# Samuel_Quenching.net
KiCad netlist of a schematic drawn in EasyEDA Pro
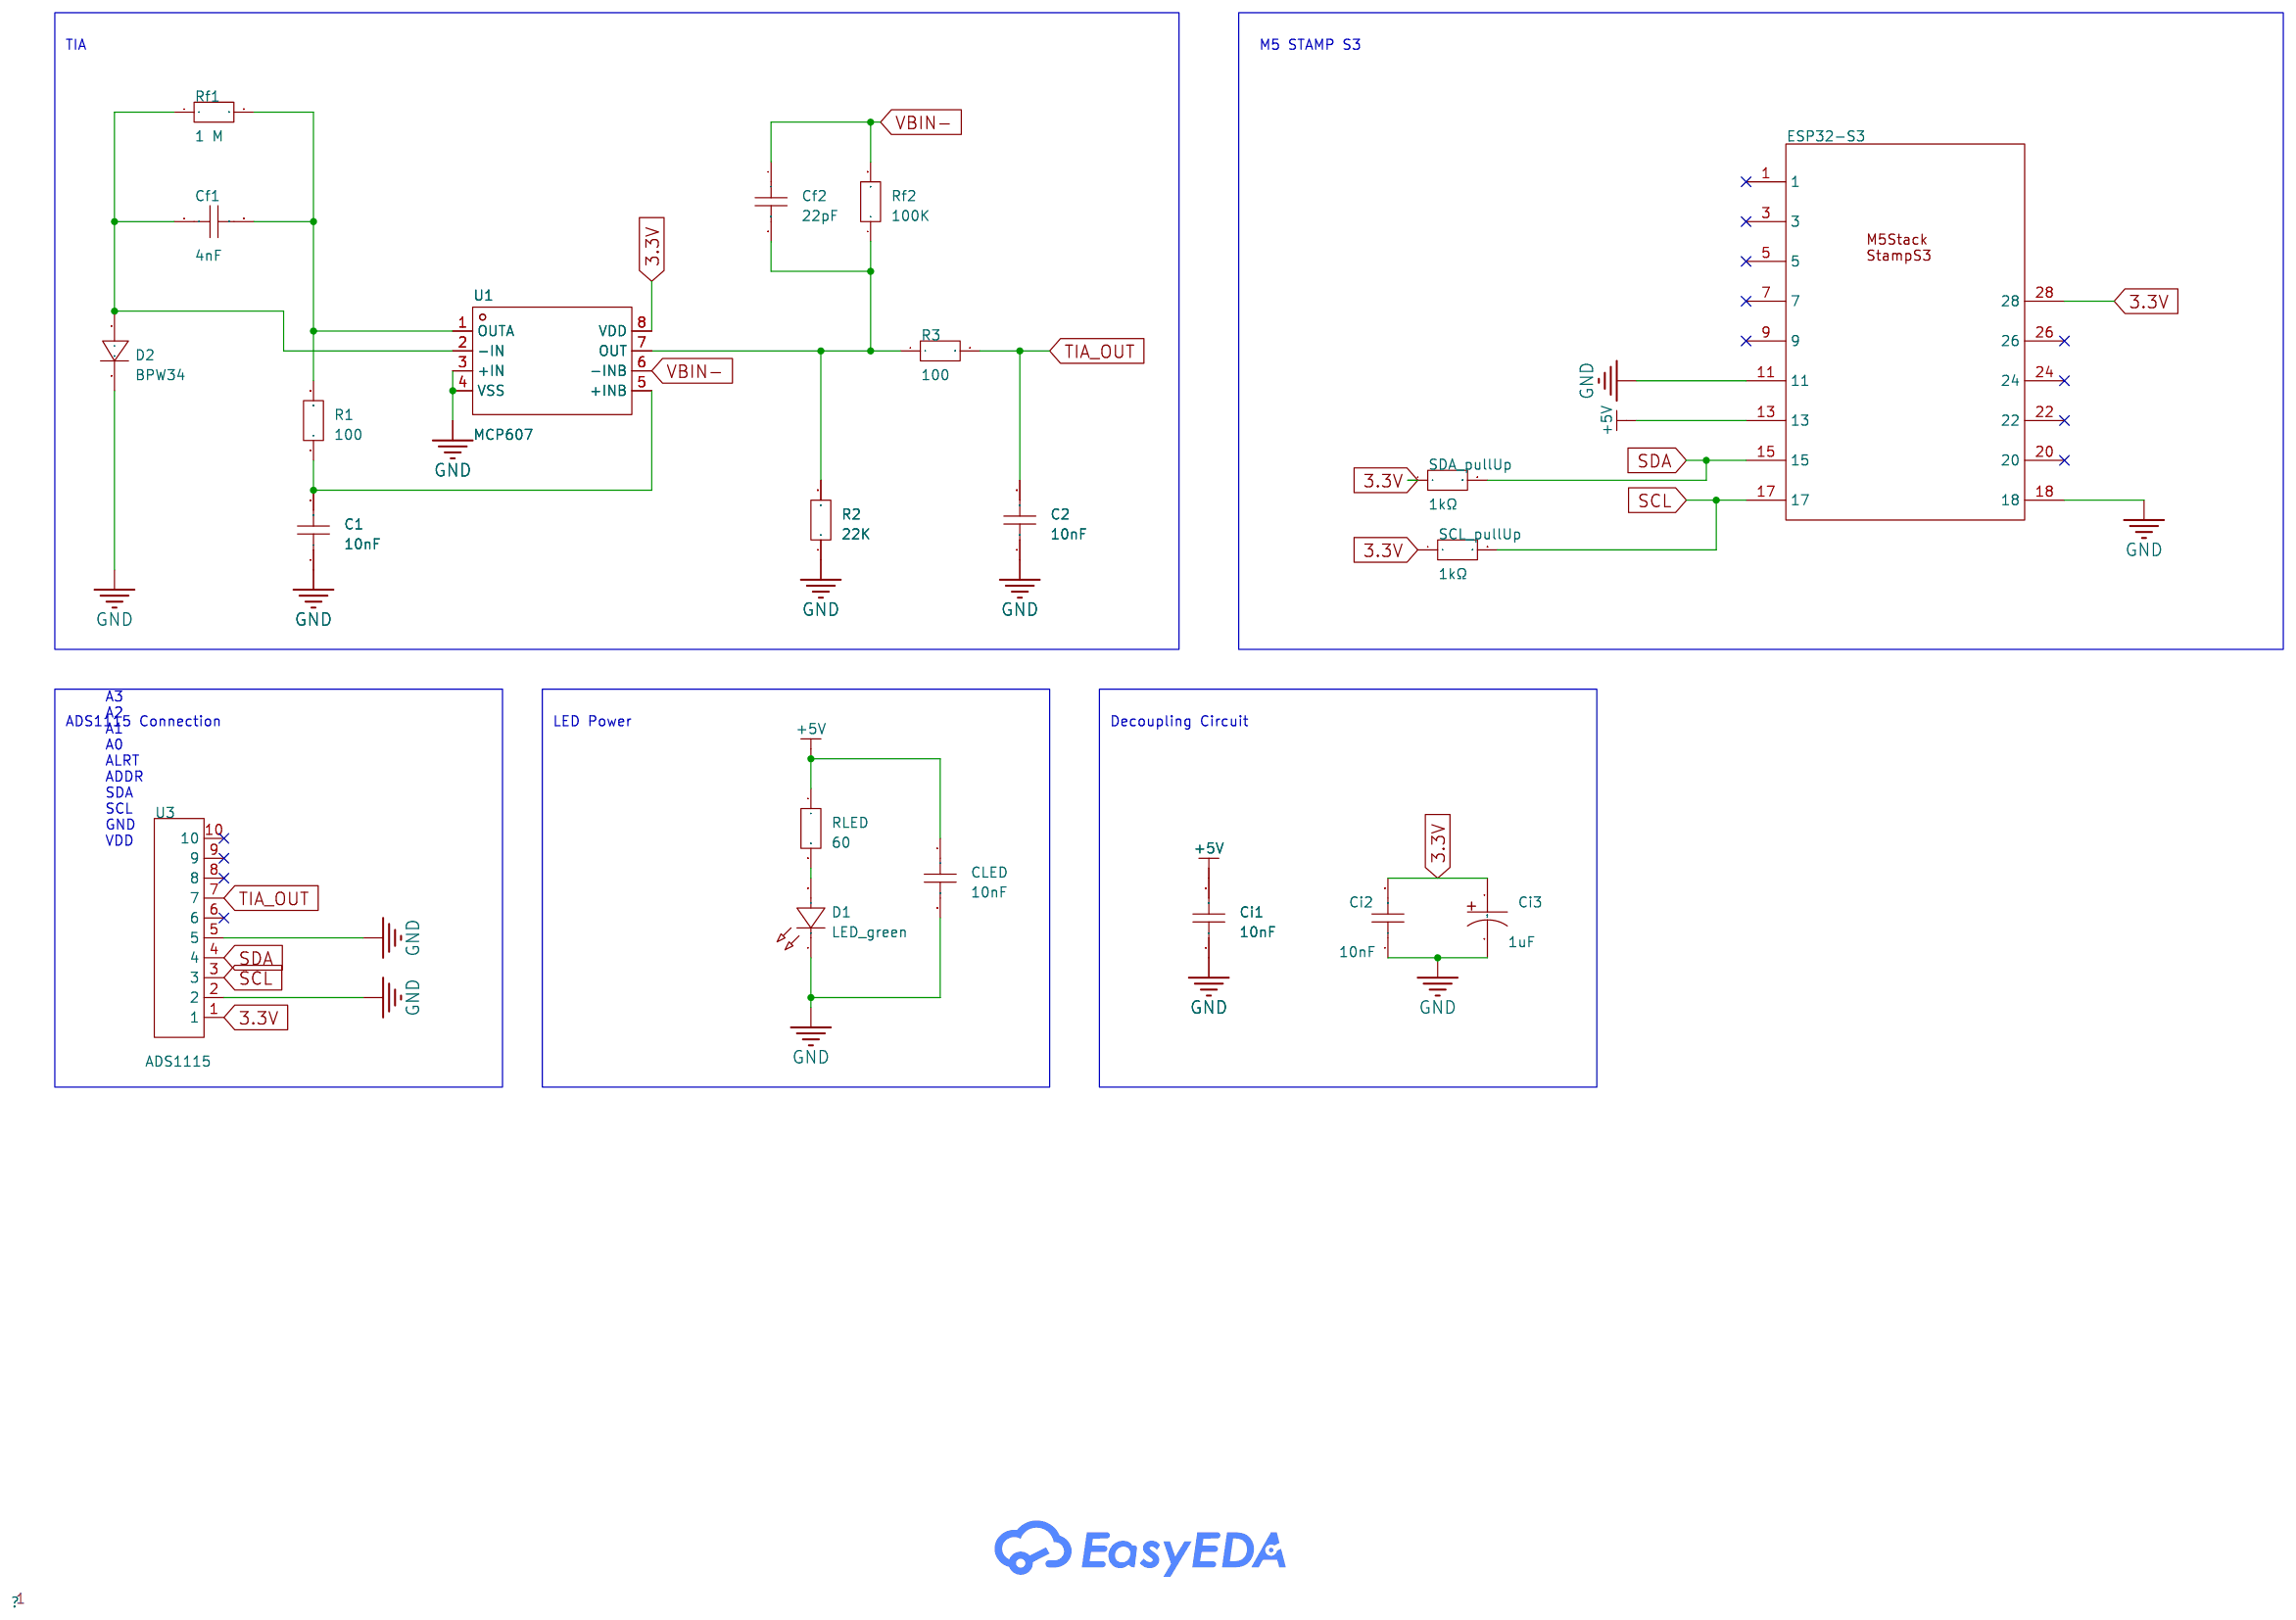
[diagram p0: schematic sheet]

(export (version "E")
  (design (tool "Eeschema 10.0.6"))
  (components
    (comp (ref "C1")
      (value "2.2nF")
      (footprint "easyedapro:CAP-TH_L6.0-W3.0-P5.00-D1.0")
      (fields (field (name "Manufacturer Part") "R06F1B222MN0B0S0N0") (field (name "Manufacturer") "STE(松田)"))
      (libsource (lib "easyedapro") (part "R06F1B222MN0B0S0N0"))
    )
    (comp (ref "C2")
      (value "2.2nF")
      (footprint "easyedapro:CAP-TH_L6.0-W3.0-P5.00-D1.0")
      (fields (field (name "Manufacturer Part") "R06F1B222MN0B0S0N0") (field (name "Manufacturer") "STE(松田)"))
      (libsource (lib "easyedapro") (part "R06F1B222MN0B0S0N0"))
    )
    (comp (ref "Cf1")
      (value "2.2nF")
      (footprint "easyedapro:CAP-TH_L6.0-W3.0-P5.00-D1.0")
      (fields (field (name "Manufacturer Part") "R06F1B222MN0B0S0N0") (field (name "Manufacturer") "STE(松田)"))
      (libsource (lib "easyedapro") (part "R06F1B222MN0B0S0N0"))
    )
    (comp (ref "Cf2")
      (value "2.2nF")
      (footprint "easyedapro:CAP-TH_L6.0-W3.0-P5.00-D1.0")
      (fields (field (name "Manufacturer Part") "R06F1B222MN0B0S0N0") (field (name "Manufacturer") "STE(松田)"))
      (libsource (lib "easyedapro") (part "R06F1B222MN0B0S0N0"))
    )
    (comp (ref "Ci1")
      (value "2.2nF")
      (footprint "easyedapro:CAP-TH_L6.0-W3.0-P5.00-D1.0")
      (fields (field (name "Manufacturer Part") "R06F1B222MN0B0S0N0") (field (name "Manufacturer") "STE(松田)"))
      (libsource (lib "easyedapro") (part "R06F1B222MN0B0S0N0"))
    )
    (comp (ref "Ci2")
      (value "2.2nF")
      (footprint "easyedapro:CAP-TH_L6.0-W3.0-P5.00-D1.0")
      (fields (field (name "Manufacturer Part") "R06F1B222MN0B0S0N0") (field (name "Manufacturer") "STE(松田)"))
      (libsource (lib "easyedapro") (part "R06F1B222MN0B0S0N0"))
    )
    (comp (ref "Ci3")
      (value "20F")
      (footprint "easyedapro:CAP-TH_BD5.0-P2.00-D0.5-FD_CD26G2AM1R0D110T")
      (fields (field (name "Manufacturer Part") "SLA3R8O2060813") (field (name "Manufacturer") "Ymin(永铭)"))
      (libsource (lib "easyedapro") (part "SLA3R8L2060813"))
    )
    (comp (ref "CLED")
      (value "2.2nF")
      (footprint "easyedapro:CAP-TH_L6.0-W3.0-P5.00-D1.0")
      (fields (field (name "Manufacturer Part") "R06F1B222MN0B0S0N0") (field (name "Manufacturer") "STE(松田)"))
      (libsource (lib "easyedapro") (part "R06F1B222MN0B0S0N0"))
    )
    (comp (ref "D1")
      (value "LED_green")
      (footprint "easyedapro:LED-TH_BD3.5-P2.28-3A2K-10")
      (fields
        (field (name "Manufacturer Part") "3A2K-10")
        (field (name "Manufacturer") "Guiguang light(桂光光电)")
      )
      (libsource (lib "easyedapro") (part "3A2K-10"))
    )
    (comp (ref "D2")
      (value "BPW34")
      (footprint "easyedapro:SENSOR-TH_BPW34")
      (fields (field (name "Manufacturer") "VISHAY(威世)"))
      (libsource (lib "easyedapro") (part "BPW34_C85128"))
    )
    (comp (ref "ESP32-S3")
      (value "U2")
      (footprint "easyedapro:M5Stack StampS3")
      (libsource (lib "easyedapro") (part "Esp-S3 M5Stamp"))
    )
    (comp (ref "R1")
      (value "1kΩ")
      (footprint "easyedapro:RES-TH_BD2.3-L6.5-P10.50-D0.5")
      (fields (field (name "Manufacturer Part") "MF1/4W-1KΩ±1%T52") (field (name "Manufacturer") "华星机电"))
      (libsource (lib "easyedapro") (part "MF1/4W-1KΩ±1%T52"))
    )
    (comp (ref "R2")
      (value "1kΩ")
      (footprint "easyedapro:RES-TH_BD2.3-L6.5-P10.50-D0.5")
      (fields (field (name "Manufacturer Part") "MF1/4W-1KΩ±1%T52") (field (name "Manufacturer") "华星机电"))
      (libsource (lib "easyedapro") (part "MF1/4W-1KΩ±1%T52"))
    )
    (comp (ref "R3")
      (value "1kΩ")
      (footprint "easyedapro:RES-TH_BD2.3-L6.5-P10.50-D0.5")
      (fields (field (name "Manufacturer Part") "MF1/4W-1KΩ±1%T52") (field (name "Manufacturer") "华星机电"))
      (libsource (lib "easyedapro") (part "MF1/4W-1KΩ±1%T52"))
    )
    (comp (ref "Rf1")
      (value "1kΩ")
      (footprint "easyedapro:RES-TH_BD2.3-L6.5-P10.50-D0.5")
      (fields (field (name "Manufacturer Part") "MF1/4W-1KΩ±1%T52") (field (name "Manufacturer") "华星机电"))
      (libsource (lib "easyedapro") (part "MF1/4W-1KΩ±1%T52"))
    )
    (comp (ref "Rf2")
      (value "1kΩ")
      (footprint "easyedapro:RES-TH_BD2.3-L6.5-P10.50-D0.5")
      (fields (field (name "Manufacturer Part") "MF1/4W-1KΩ±1%T52") (field (name "Manufacturer") "华星机电"))
      (libsource (lib "easyedapro") (part "MF1/4W-1KΩ±1%T52"))
    )
    (comp (ref "RLED")
      (value "1kΩ")
      (footprint "easyedapro:RES-TH_BD2.3-L6.5-P10.50-D0.5")
      (fields (field (name "Manufacturer Part") "MF1/4W-1KΩ±1%T52") (field (name "Manufacturer") "华星机电"))
      (libsource (lib "easyedapro") (part "MF1/4W-1KΩ±1%T52"))
    )
    (comp (ref "SCL_pullUp")
      (value "1kΩ")
      (footprint "easyedapro:RES-TH_BD2.3-L6.5-P10.50-D0.5")
      (fields (field (name "Manufacturer Part") "MF1/4W-1KΩ±1%T52") (field (name "Manufacturer") "华星机电"))
      (libsource (lib "easyedapro") (part "MF1/4W-1KΩ±1%T52"))
    )
    (comp (ref "SDA_pullUp")
      (value "1kΩ")
      (footprint "easyedapro:RES-TH_BD2.3-L6.5-P10.50-D0.5")
      (fields (field (name "Manufacturer Part") "MF1/4W-1KΩ±1%T52") (field (name "Manufacturer") "华星机电"))
      (libsource (lib "easyedapro") (part "MF1/4W-1KΩ±1%T52"))
    )
    (comp (ref "U1")
      (value "MCP607")
      (footprint "easyedapro:DIP-8_L9.4-W6.4-P2.54-LS9.1-BL")
      (fields (field (name "Manufacturer Part") "MCP607-I/P") (field (name "Manufacturer") "MICROCHIP(美国微芯)"))
      (libsource (lib "easyedapro") (part "MCP607-I/P"))
    )
    (comp (ref "U3")
      (value "ADS1115")
      (footprint "easyedapro:HDR-TH_10P-P2.54-V-M-1")
      (fields (field (name "Manufacturer Part") "2.54-1*10P针") (field (name "Manufacturer") "BOOMELE(博穆精密)"))
      (libsource (lib "easyedapro") (part "Header-Male-2.54_1x10"))
    )
  )
  (nets
    (net (code "1") (name "+5V") (class "Default")
      (node (ref "CLED") (pin "1") (pinfunction "1_1") (pintype "unspecified"))
      (node (ref "Ci1") (pin "2") (pinfunction "2_2") (pintype "unspecified"))
      (node (ref "ESP32-S3") (pin "13") (pinfunction "13_13") (pintype "input"))
      (node (ref "RLED") (pin "1") (pinfunction "1_1") (pintype "unspecified"))
    )
    (net (code "2") (name "3.3V") (class "Default")
      (node (ref "Ci2") (pin "2") (pinfunction "2_2") (pintype "unspecified"))
      (node (ref "Ci3") (pin "1") (pinfunction "1_1") (pintype "unspecified"))
      (node (ref "ESP32-S3") (pin "28") (pinfunction "28_28") (pintype "input"))
      (node (ref "SCL_pullUp") (pin "1") (pinfunction "1_1") (pintype "unspecified"))
      (node (ref "SDA_pullUp") (pin "1") (pinfunction "1_1") (pintype "unspecified"))
      (node (ref "U1") (pin "8") (pinfunction "VDD_8") (pintype "input"))
      (node (ref "U3") (pin "1") (pinfunction "1_1") (pintype "unspecified"))
    )
    (net (code "3") (name "GND") (class "Default")
      (node (ref "C1") (pin "1") (pinfunction "1_1") (pintype "unspecified"))
      (node (ref "C2") (pin "1") (pinfunction "1_1") (pintype "unspecified"))
      (node (ref "CLED") (pin "2") (pinfunction "2_2") (pintype "unspecified"))
      (node (ref "Ci1") (pin "1") (pinfunction "1_1") (pintype "unspecified"))
      (node (ref "Ci2") (pin "1") (pinfunction "1_1") (pintype "unspecified"))
      (node (ref "Ci3") (pin "2") (pinfunction "2_2") (pintype "unspecified"))
      (node (ref "D1") (pin "1") (pinfunction "C_1") (pintype "unspecified"))
      (node (ref "D2") (pin "2") (pinfunction "C_2") (pintype "unspecified"))
      (node (ref "ESP32-S3") (pin "11") (pinfunction "11_11") (pintype "input"))
      (node (ref "ESP32-S3") (pin "18") (pinfunction "18_18") (pintype "input"))
      (node (ref "R2") (pin "1") (pinfunction "1_1") (pintype "unspecified"))
      (node (ref "U1") (pin "3") (pinfunction "+IN_3") (pintype "input"))
      (node (ref "U1") (pin "4") (pinfunction "VSS_4") (pintype "input"))
      (node (ref "U3") (pin "2") (pinfunction "2_2") (pintype "unspecified"))
      (node (ref "U3") (pin "5") (pinfunction "5_5") (pintype "unspecified"))
    )
    (net (code "4") (name "Net-(D1-A)") (class "Default")
      (node (ref "D1") (pin "2") (pinfunction "A_2") (pintype "unspecified"))
      (node (ref "RLED") (pin "2") (pinfunction "2_2") (pintype "unspecified"))
    )
    (net (code "5") (name "Net-(D2-A)") (class "Default")
      (node (ref "Cf1") (pin "1") (pinfunction "1_1") (pintype "unspecified"))
      (node (ref "D2") (pin "1") (pinfunction "A_1") (pintype "unspecified"))
      (node (ref "Rf1") (pin "1") (pinfunction "1_1") (pintype "unspecified"))
      (node (ref "U1") (pin "2") (pinfunction "-IN_2") (pintype "input"))
    )
    (net (code "6") (name "Net-(U1-+INB)") (class "Default")
      (node (ref "C1") (pin "2") (pinfunction "2_2") (pintype "unspecified"))
      (node (ref "R1") (pin "1") (pinfunction "1_1") (pintype "unspecified"))
      (node (ref "U1") (pin "5") (pinfunction "+INB_5") (pintype "input"))
    )
    (net (code "7") (name "Net-(U1-OUT)") (class "Default")
      (node (ref "Cf2") (pin "2") (pinfunction "2_2") (pintype "unspecified"))
      (node (ref "R2") (pin "2") (pinfunction "2_2") (pintype "unspecified"))
      (node (ref "R3") (pin "1") (pinfunction "1_1") (pintype "unspecified"))
      (node (ref "Rf2") (pin "1") (pinfunction "1_1") (pintype "unspecified"))
      (node (ref "U1") (pin "7") (pinfunction "OUT_7") (pintype "input"))
    )
    (net (code "8") (name "Net-(U1-OUTA)") (class "Default")
      (node (ref "Cf1") (pin "2") (pinfunction "2_2") (pintype "unspecified"))
      (node (ref "R1") (pin "2") (pinfunction "2_2") (pintype "unspecified"))
      (node (ref "Rf1") (pin "2") (pinfunction "2_2") (pintype "unspecified"))
      (node (ref "U1") (pin "1") (pinfunction "OUTA_1") (pintype "input"))
    )
    (net (code "9") (name "SCL") (class "Default")
      (node (ref "ESP32-S3") (pin "17") (pinfunction "17_17") (pintype "input"))
      (node (ref "SCL_pullUp") (pin "2") (pinfunction "2_2") (pintype "unspecified"))
      (node (ref "U3") (pin "3") (pinfunction "3_3") (pintype "unspecified"))
    )
    (net (code "10") (name "SDA") (class "Default")
      (node (ref "ESP32-S3") (pin "15") (pinfunction "15_15") (pintype "input"))
      (node (ref "SDA_pullUp") (pin "2") (pinfunction "2_2") (pintype "unspecified"))
      (node (ref "U3") (pin "4") (pinfunction "4_4") (pintype "unspecified"))
    )
    (net (code "11") (name "TIA_OUT") (class "Default")
      (node (ref "C2") (pin "2") (pinfunction "2_2") (pintype "unspecified"))
      (node (ref "R3") (pin "2") (pinfunction "2_2") (pintype "unspecified"))
      (node (ref "U3") (pin "7") (pinfunction "7_7") (pintype "unspecified"))
    )
    (net (code "12") (name "VBIN-") (class "Default")
      (node (ref "Cf2") (pin "1") (pinfunction "1_1") (pintype "unspecified"))
      (node (ref "Rf2") (pin "2") (pinfunction "2_2") (pintype "unspecified"))
      (node (ref "U1") (pin "6") (pinfunction "-INB_6") (pintype "input"))
    )
    (net (code "13") (name "unconnected-(ESP32-S3-Pad1)") (class "Default")
      (node (ref "ESP32-S3") (pin "1") (pinfunction "1_1") (pintype "input+no_connect"))
    )
    (net (code "14") (name "unconnected-(ESP32-S3-Pad3)") (class "Default")
      (node (ref "ESP32-S3") (pin "3") (pinfunction "3_3") (pintype "input+no_connect"))
    )
    (net (code "15") (name "unconnected-(ESP32-S3-Pad5)") (class "Default")
      (node (ref "ESP32-S3") (pin "5") (pinfunction "5_5") (pintype "input+no_connect"))
    )
    (net (code "16") (name "unconnected-(ESP32-S3-Pad7)") (class "Default")
      (node (ref "ESP32-S3") (pin "7") (pinfunction "7_7") (pintype "input+no_connect"))
    )
    (net (code "17") (name "unconnected-(ESP32-S3-Pad9)") (class "Default")
      (node (ref "ESP32-S3") (pin "9") (pinfunction "9_9") (pintype "input+no_connect"))
    )
    (net (code "18") (name "unconnected-(ESP32-S3-Pad20)") (class "Default")
      (node (ref "ESP32-S3") (pin "20") (pinfunction "20_20") (pintype "input+no_connect"))
    )
    (net (code "19") (name "unconnected-(ESP32-S3-Pad22)") (class "Default")
      (node (ref "ESP32-S3") (pin "22") (pinfunction "22_22") (pintype "input+no_connect"))
    )
    (net (code "20") (name "unconnected-(ESP32-S3-Pad24)") (class "Default")
      (node (ref "ESP32-S3") (pin "24") (pinfunction "24_24") (pintype "input+no_connect"))
    )
    (net (code "21") (name "unconnected-(ESP32-S3-Pad26)") (class "Default")
      (node (ref "ESP32-S3") (pin "26") (pinfunction "26_26") (pintype "input+no_connect"))
    )
    (net (code "22") (name "unconnected-(U3-Pad6)") (class "Default")
      (node (ref "U3") (pin "6") (pinfunction "6_6") (pintype "unspecified+no_connect"))
    )
    (net (code "23") (name "unconnected-(U3-Pad8)") (class "Default")
      (node (ref "U3") (pin "8") (pinfunction "8_8") (pintype "unspecified+no_connect"))
    )
    (net (code "24") (name "unconnected-(U3-Pad9)") (class "Default")
      (node (ref "U3") (pin "9") (pinfunction "9_9") (pintype "unspecified+no_connect"))
    )
    (net (code "25") (name "unconnected-(U3-Pad10)") (class "Default")
      (node (ref "U3") (pin "10") (pinfunction "10_10") (pintype "unspecified+no_connect"))
    )
  )
)
